# io2.net
KiCad netlist of a schematic drawn in EAGLE
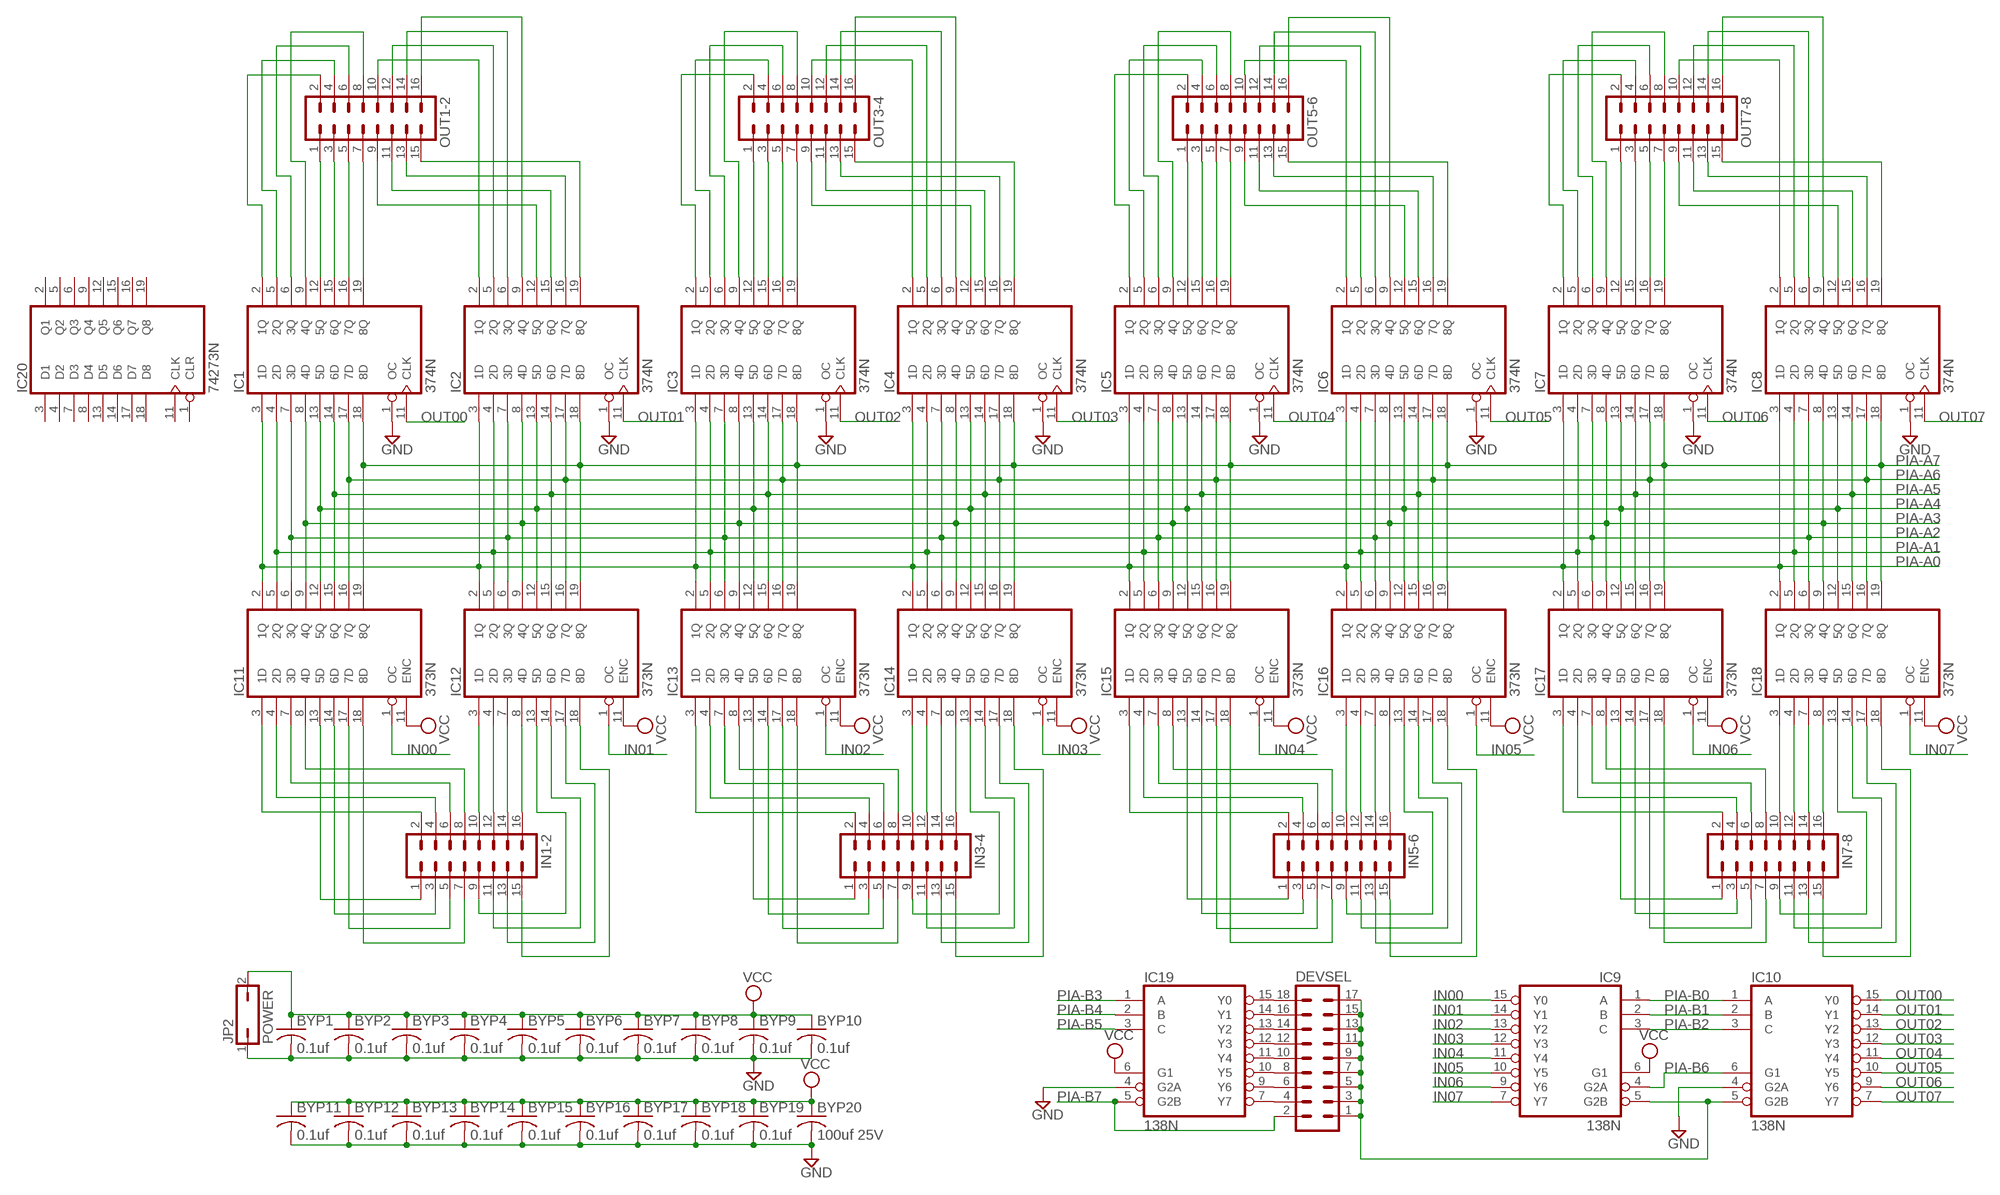
[diagram p0: schematic, sheet 1]
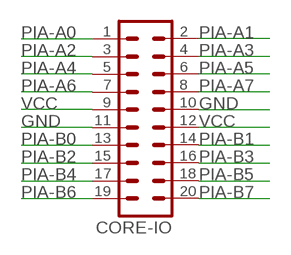
[diagram p1: schematic, sheet 2]

(export (version "E")
  (design (tool "Eeschema 10.0.6"))
  (components
    (comp (ref "CORE-IO")
      (value "MA10-2")
      (footprint "eagle-import:MA10-2")
      (libsource (lib "eagle-import") (part "MA10-2"))
    )
    (comp (ref "BYP1")
      (value "0.1uf")
      (footprint "eagle-import:C050-025X075")
      (libsource (lib "eagle-import") (part "C-US050-025X075"))
    )
    (comp (ref "BYP2")
      (value "0.1uf")
      (footprint "eagle-import:C050-025X075")
      (libsource (lib "eagle-import") (part "C-US050-025X075"))
    )
    (comp (ref "BYP3")
      (value "0.1uf")
      (footprint "eagle-import:C050-025X075")
      (libsource (lib "eagle-import") (part "C-US050-025X075"))
    )
    (comp (ref "BYP4")
      (value "0.1uf")
      (footprint "eagle-import:C050-025X075")
      (libsource (lib "eagle-import") (part "C-US050-025X075"))
    )
    (comp (ref "BYP5")
      (value "0.1uf")
      (footprint "eagle-import:C050-025X075")
      (libsource (lib "eagle-import") (part "C-US050-025X075"))
    )
    (comp (ref "BYP6")
      (value "0.1uf")
      (footprint "eagle-import:C050-025X075")
      (libsource (lib "eagle-import") (part "C-US050-025X075"))
    )
    (comp (ref "BYP7")
      (value "0.1uf")
      (footprint "eagle-import:C050-025X075")
      (libsource (lib "eagle-import") (part "C-US050-025X075"))
    )
    (comp (ref "BYP8")
      (value "0.1uf")
      (footprint "eagle-import:C050-025X075")
      (libsource (lib "eagle-import") (part "C-US050-025X075"))
    )
    (comp (ref "BYP9")
      (value "0.1uf")
      (footprint "eagle-import:C050-025X075")
      (libsource (lib "eagle-import") (part "C-US050-025X075"))
    )
    (comp (ref "BYP10")
      (value "0.1uf")
      (footprint "eagle-import:C050-025X075")
      (libsource (lib "eagle-import") (part "C-US050-025X075"))
    )
    (comp (ref "BYP11")
      (value "0.1uf")
      (footprint "eagle-import:C050-025X075")
      (libsource (lib "eagle-import") (part "C-US050-025X075"))
    )
    (comp (ref "BYP12")
      (value "0.1uf")
      (footprint "eagle-import:C050-025X075")
      (libsource (lib "eagle-import") (part "C-US050-025X075"))
    )
    (comp (ref "BYP13")
      (value "0.1uf")
      (footprint "eagle-import:C050-025X075")
      (libsource (lib "eagle-import") (part "C-US050-025X075"))
    )
    (comp (ref "BYP14")
      (value "0.1uf")
      (footprint "eagle-import:C050-025X075")
      (libsource (lib "eagle-import") (part "C-US050-025X075"))
    )
    (comp (ref "BYP15")
      (value "0.1uf")
      (footprint "eagle-import:C050-025X075")
      (libsource (lib "eagle-import") (part "C-US050-025X075"))
    )
    (comp (ref "BYP16")
      (value "0.1uf")
      (footprint "eagle-import:C050-025X075")
      (libsource (lib "eagle-import") (part "C-US050-025X075"))
    )
    (comp (ref "BYP17")
      (value "0.1uf")
      (footprint "eagle-import:C050-025X075")
      (libsource (lib "eagle-import") (part "C-US050-025X075"))
    )
    (comp (ref "BYP18")
      (value "0.1uf")
      (footprint "eagle-import:C050-025X075")
      (libsource (lib "eagle-import") (part "C-US050-025X075"))
    )
    (comp (ref "BYP19")
      (value "0.1uf")
      (footprint "eagle-import:C050-025X075")
      (libsource (lib "eagle-import") (part "C-US050-025X075"))
    )
    (comp (ref "BYP20")
      (value "100uf 25V")
      (footprint "eagle-import:C150-064X183")
      (libsource (lib "eagle-import") (part "C-US150-064X183"))
    )
    (comp (ref "DEVSEL")
      (value "MA09-2")
      (footprint "eagle-import:MA09-2")
      (libsource (lib "eagle-import") (part "MA09-2"))
    )
    (comp (ref "IC1")
      (value "374N")
      (footprint "eagle-import:DIL20")
      (libsource (lib "eagle-import") (part "74374NLS"))
    )
    (comp (ref "IC2")
      (value "374N")
      (footprint "eagle-import:DIL20")
      (libsource (lib "eagle-import") (part "74374NLS"))
    )
    (comp (ref "IC3")
      (value "374N")
      (footprint "eagle-import:DIL20")
      (libsource (lib "eagle-import") (part "74374NLS"))
    )
    (comp (ref "IC4")
      (value "374N")
      (footprint "eagle-import:DIL20")
      (libsource (lib "eagle-import") (part "74374NLS"))
    )
    (comp (ref "IC5")
      (value "374N")
      (footprint "eagle-import:DIL20")
      (libsource (lib "eagle-import") (part "74374NLS"))
    )
    (comp (ref "IC6")
      (value "374N")
      (footprint "eagle-import:DIL20")
      (libsource (lib "eagle-import") (part "74374NLS"))
    )
    (comp (ref "IC7")
      (value "374N")
      (footprint "eagle-import:DIL20")
      (libsource (lib "eagle-import") (part "74374NLS"))
    )
    (comp (ref "IC8")
      (value "374N")
      (footprint "eagle-import:DIL20")
      (libsource (lib "eagle-import") (part "74374NLS"))
    )
    (comp (ref "IC9")
      (value "138N")
      (footprint "eagle-import:DIL16")
      (libsource (lib "eagle-import") (part "74138NLS"))
    )
    (comp (ref "IC10")
      (value "138N")
      (footprint "eagle-import:DIL16")
      (libsource (lib "eagle-import") (part "74138NLS"))
    )
    (comp (ref "IC11")
      (value "373N")
      (footprint "eagle-import:DIL20")
      (libsource (lib "eagle-import") (part "74373NLS"))
    )
    (comp (ref "IC12")
      (value "373N")
      (footprint "eagle-import:DIL20")
      (libsource (lib "eagle-import") (part "74373NLS"))
    )
    (comp (ref "IC13")
      (value "373N")
      (footprint "eagle-import:DIL20")
      (libsource (lib "eagle-import") (part "74373NLS"))
    )
    (comp (ref "IC14")
      (value "373N")
      (footprint "eagle-import:DIL20")
      (libsource (lib "eagle-import") (part "74373NLS"))
    )
    (comp (ref "IC15")
      (value "373N")
      (footprint "eagle-import:DIL20")
      (libsource (lib "eagle-import") (part "74373NLS"))
    )
    (comp (ref "IC16")
      (value "373N")
      (footprint "eagle-import:DIL20")
      (libsource (lib "eagle-import") (part "74373NLS"))
    )
    (comp (ref "IC17")
      (value "373N")
      (footprint "eagle-import:DIL20")
      (libsource (lib "eagle-import") (part "74373NLS"))
    )
    (comp (ref "IC18")
      (value "373N")
      (footprint "eagle-import:DIL20")
      (libsource (lib "eagle-import") (part "74373NLS"))
    )
    (comp (ref "IC19")
      (value "138N")
      (footprint "eagle-import:DIL16")
      (libsource (lib "eagle-import") (part "74138NLS"))
    )
    (comp (ref "IC20")
      (value "74273N")
      (footprint "eagle-import:DIL20")
      (libsource (lib "eagle-import") (part "74273N"))
    )
    (comp (ref "IN1-2")
      (value "MA08-2")
      (footprint "eagle-import:MA08-2")
      (libsource (lib "eagle-import") (part "MA08-2"))
    )
    (comp (ref "IN3-4")
      (value "MA08-2")
      (footprint "eagle-import:MA08-2")
      (libsource (lib "eagle-import") (part "MA08-2"))
    )
    (comp (ref "IN5-6")
      (value "MA08-2")
      (footprint "eagle-import:MA08-2")
      (libsource (lib "eagle-import") (part "MA08-2"))
    )
    (comp (ref "IN7-8")
      (value "MA08-2")
      (footprint "eagle-import:MA08-2")
      (libsource (lib "eagle-import") (part "MA08-2"))
    )
    (comp (ref "JP2")
      (value "POWER")
      (footprint "eagle-import:JP1")
      (libsource (lib "eagle-import") (part "JP1Q"))
    )
    (comp (ref "OUT1-2")
      (value "MA08-2")
      (footprint "eagle-import:MA08-2")
      (libsource (lib "eagle-import") (part "MA08-2"))
    )
    (comp (ref "OUT3-4")
      (value "MA08-2")
      (footprint "eagle-import:MA08-2")
      (libsource (lib "eagle-import") (part "MA08-2"))
    )
    (comp (ref "OUT5-6")
      (value "MA08-2")
      (footprint "eagle-import:MA08-2")
      (libsource (lib "eagle-import") (part "MA08-2"))
    )
    (comp (ref "OUT7-8")
      (value "MA08-2")
      (footprint "eagle-import:MA08-2")
      (libsource (lib "eagle-import") (part "MA08-2"))
    )
  )
  (nets
    (net (code "1") (name "GND") (class "Default")
      (node (ref "BYP1") (pin "2") (pinfunction "2_2") (pintype "passive"))
      (node (ref "BYP10") (pin "2") (pinfunction "2_2") (pintype "passive"))
      (node (ref "BYP11") (pin "2") (pinfunction "2_2") (pintype "passive"))
      (node (ref "BYP12") (pin "2") (pinfunction "2_2") (pintype "passive"))
      (node (ref "BYP13") (pin "2") (pinfunction "2_2") (pintype "passive"))
      (node (ref "BYP14") (pin "2") (pinfunction "2_2") (pintype "passive"))
      (node (ref "BYP15") (pin "2") (pinfunction "2_2") (pintype "passive"))
      (node (ref "BYP16") (pin "2") (pinfunction "2_2") (pintype "passive"))
      (node (ref "BYP17") (pin "2") (pinfunction "2_2") (pintype "passive"))
      (node (ref "BYP18") (pin "2") (pinfunction "2_2") (pintype "passive"))
      (node (ref "BYP19") (pin "2") (pinfunction "2_2") (pintype "passive"))
      (node (ref "BYP2") (pin "2") (pinfunction "2_2") (pintype "passive"))
      (node (ref "BYP20") (pin "2") (pinfunction "2_2") (pintype "passive"))
      (node (ref "BYP3") (pin "2") (pinfunction "2_2") (pintype "passive"))
      (node (ref "BYP4") (pin "2") (pinfunction "2_2") (pintype "passive"))
      (node (ref "BYP5") (pin "2") (pinfunction "2_2") (pintype "passive"))
      (node (ref "BYP6") (pin "2") (pinfunction "2_2") (pintype "passive"))
      (node (ref "BYP7") (pin "2") (pinfunction "2_2") (pintype "passive"))
      (node (ref "BYP8") (pin "2") (pinfunction "2_2") (pintype "passive"))
      (node (ref "BYP9") (pin "2") (pinfunction "2_2") (pintype "passive"))
      (node (ref "CORE-IO") (pin "10") (pinfunction "10_10") (pintype "passive"))
      (node (ref "CORE-IO") (pin "11") (pinfunction "11_11") (pintype "passive"))
      (node (ref "IC1") (pin "1") (pinfunction "OC_1") (pintype "input"))
      (node (ref "IC10") (pin "4") (pinfunction "G2A_4") (pintype "input"))
      (node (ref "IC19") (pin "4") (pinfunction "G2A_4") (pintype "input"))
      (node (ref "IC2") (pin "1") (pinfunction "OC_1") (pintype "input"))
      (node (ref "IC3") (pin "1") (pinfunction "OC_1") (pintype "input"))
      (node (ref "IC4") (pin "1") (pinfunction "OC_1") (pintype "input"))
      (node (ref "IC5") (pin "1") (pinfunction "OC_1") (pintype "input"))
      (node (ref "IC6") (pin "1") (pinfunction "OC_1") (pintype "input"))
      (node (ref "IC7") (pin "1") (pinfunction "OC_1") (pintype "input"))
      (node (ref "IC8") (pin "1") (pinfunction "OC_1") (pintype "input"))
      (node (ref "JP2") (pin "1") (pinfunction "1_1") (pintype "passive"))
    )
    (net (code "2") (name "IN00") (class "Default")
      (node (ref "IC11") (pin "1") (pinfunction "OC_1") (pintype "input"))
      (node (ref "IC9") (pin "15") (pinfunction "Y0_15") (pintype "output"))
    )
    (net (code "3") (name "IN01") (class "Default")
      (node (ref "IC12") (pin "1") (pinfunction "OC_1") (pintype "input"))
      (node (ref "IC9") (pin "14") (pinfunction "Y1_14") (pintype "output"))
    )
    (net (code "4") (name "IN02") (class "Default")
      (node (ref "IC13") (pin "1") (pinfunction "OC_1") (pintype "input"))
      (node (ref "IC9") (pin "13") (pinfunction "Y2_13") (pintype "output"))
    )
    (net (code "5") (name "IN03") (class "Default")
      (node (ref "IC14") (pin "1") (pinfunction "OC_1") (pintype "input"))
      (node (ref "IC9") (pin "12") (pinfunction "Y3_12") (pintype "output"))
    )
    (net (code "6") (name "IN04") (class "Default")
      (node (ref "IC15") (pin "1") (pinfunction "OC_1") (pintype "input"))
      (node (ref "IC9") (pin "11") (pinfunction "Y4_11") (pintype "output"))
    )
    (net (code "7") (name "IN05") (class "Default")
      (node (ref "IC16") (pin "1") (pinfunction "OC_1") (pintype "input"))
      (node (ref "IC9") (pin "10") (pinfunction "Y5_10") (pintype "output"))
    )
    (net (code "8") (name "IN06") (class "Default")
      (node (ref "IC17") (pin "1") (pinfunction "OC_1") (pintype "input"))
      (node (ref "IC9") (pin "9") (pinfunction "Y6_9") (pintype "output"))
    )
    (net (code "9") (name "IN07") (class "Default")
      (node (ref "IC18") (pin "1") (pinfunction "OC_1") (pintype "input"))
      (node (ref "IC9") (pin "7") (pinfunction "Y7_7") (pintype "output"))
    )
    (net (code "10") (name "Net-(IC1A-1Q)") (class "Default")
      (node (ref "IC1") (pin "2") (pinfunction "1Q_2") (pintype "tri_state"))
      (node (ref "OUT1-2") (pin "2") (pinfunction "2_2") (pintype "passive"))
    )
    (net (code "11") (name "Net-(IC1A-2Q)") (class "Default")
      (node (ref "IC1") (pin "5") (pinfunction "2Q_5") (pintype "tri_state"))
      (node (ref "OUT1-2") (pin "4") (pinfunction "4_4") (pintype "passive"))
    )
    (net (code "12") (name "Net-(IC1A-3Q)") (class "Default")
      (node (ref "IC1") (pin "6") (pinfunction "3Q_6") (pintype "tri_state"))
      (node (ref "OUT1-2") (pin "6") (pinfunction "6_6") (pintype "passive"))
    )
    (net (code "13") (name "Net-(IC1A-4Q)") (class "Default")
      (node (ref "IC1") (pin "9") (pinfunction "4Q_9") (pintype "tri_state"))
      (node (ref "OUT1-2") (pin "8") (pinfunction "8_8") (pintype "passive"))
    )
    (net (code "14") (name "Net-(IC1A-5Q)") (class "Default")
      (node (ref "IC1") (pin "12") (pinfunction "5Q_12") (pintype "tri_state"))
      (node (ref "OUT1-2") (pin "1") (pinfunction "1_1") (pintype "passive"))
    )
    (net (code "15") (name "Net-(IC1A-6Q)") (class "Default")
      (node (ref "IC1") (pin "15") (pinfunction "6Q_15") (pintype "tri_state"))
      (node (ref "OUT1-2") (pin "3") (pinfunction "3_3") (pintype "passive"))
    )
    (net (code "16") (name "Net-(IC1A-7Q)") (class "Default")
      (node (ref "IC1") (pin "16") (pinfunction "7Q_16") (pintype "tri_state"))
      (node (ref "OUT1-2") (pin "5") (pinfunction "5_5") (pintype "passive"))
    )
    (net (code "17") (name "Net-(IC1A-8Q)") (class "Default")
      (node (ref "IC1") (pin "19") (pinfunction "8Q_19") (pintype "tri_state"))
      (node (ref "OUT1-2") (pin "7") (pinfunction "7_7") (pintype "passive"))
    )
    (net (code "18") (name "Net-(IC2A-1Q)") (class "Default")
      (node (ref "IC2") (pin "2") (pinfunction "1Q_2") (pintype "tri_state"))
      (node (ref "OUT1-2") (pin "10") (pinfunction "10_10") (pintype "passive"))
    )
    (net (code "19") (name "Net-(IC2A-2Q)") (class "Default")
      (node (ref "IC2") (pin "5") (pinfunction "2Q_5") (pintype "tri_state"))
      (node (ref "OUT1-2") (pin "12") (pinfunction "12_12") (pintype "passive"))
    )
    (net (code "20") (name "Net-(IC2A-3Q)") (class "Default")
      (node (ref "IC2") (pin "6") (pinfunction "3Q_6") (pintype "tri_state"))
      (node (ref "OUT1-2") (pin "14") (pinfunction "14_14") (pintype "passive"))
    )
    (net (code "21") (name "Net-(IC2A-4Q)") (class "Default")
      (node (ref "IC2") (pin "9") (pinfunction "4Q_9") (pintype "tri_state"))
      (node (ref "OUT1-2") (pin "16") (pinfunction "16_16") (pintype "passive"))
    )
    (net (code "22") (name "Net-(IC2A-5Q)") (class "Default")
      (node (ref "IC2") (pin "12") (pinfunction "5Q_12") (pintype "tri_state"))
      (node (ref "OUT1-2") (pin "9") (pinfunction "9_9") (pintype "passive"))
    )
    (net (code "23") (name "Net-(IC2A-6Q)") (class "Default")
      (node (ref "IC2") (pin "15") (pinfunction "6Q_15") (pintype "tri_state"))
      (node (ref "OUT1-2") (pin "11") (pinfunction "11_11") (pintype "passive"))
    )
    (net (code "24") (name "Net-(IC2A-7Q)") (class "Default")
      (node (ref "IC2") (pin "16") (pinfunction "7Q_16") (pintype "tri_state"))
      (node (ref "OUT1-2") (pin "13") (pinfunction "13_13") (pintype "passive"))
    )
    (net (code "25") (name "Net-(IC2A-8Q)") (class "Default")
      (node (ref "IC2") (pin "19") (pinfunction "8Q_19") (pintype "tri_state"))
      (node (ref "OUT1-2") (pin "15") (pinfunction "15_15") (pintype "passive"))
    )
    (net (code "26") (name "Net-(IC3A-1Q)") (class "Default")
      (node (ref "IC3") (pin "2") (pinfunction "1Q_2") (pintype "tri_state"))
      (node (ref "OUT3-4") (pin "2") (pinfunction "2_2") (pintype "passive"))
    )
    (net (code "27") (name "Net-(IC3A-2Q)") (class "Default")
      (node (ref "IC3") (pin "5") (pinfunction "2Q_5") (pintype "tri_state"))
      (node (ref "OUT3-4") (pin "4") (pinfunction "4_4") (pintype "passive"))
    )
    (net (code "28") (name "Net-(IC3A-3Q)") (class "Default")
      (node (ref "IC3") (pin "6") (pinfunction "3Q_6") (pintype "tri_state"))
      (node (ref "OUT3-4") (pin "6") (pinfunction "6_6") (pintype "passive"))
    )
    (net (code "29") (name "Net-(IC3A-4Q)") (class "Default")
      (node (ref "IC3") (pin "9") (pinfunction "4Q_9") (pintype "tri_state"))
      (node (ref "OUT3-4") (pin "8") (pinfunction "8_8") (pintype "passive"))
    )
    (net (code "30") (name "Net-(IC3A-5Q)") (class "Default")
      (node (ref "IC3") (pin "12") (pinfunction "5Q_12") (pintype "tri_state"))
      (node (ref "OUT3-4") (pin "1") (pinfunction "1_1") (pintype "passive"))
    )
    (net (code "31") (name "Net-(IC3A-6Q)") (class "Default")
      (node (ref "IC3") (pin "15") (pinfunction "6Q_15") (pintype "tri_state"))
      (node (ref "OUT3-4") (pin "3") (pinfunction "3_3") (pintype "passive"))
    )
    (net (code "32") (name "Net-(IC3A-7Q)") (class "Default")
      (node (ref "IC3") (pin "16") (pinfunction "7Q_16") (pintype "tri_state"))
      (node (ref "OUT3-4") (pin "5") (pinfunction "5_5") (pintype "passive"))
    )
    (net (code "33") (name "Net-(IC3A-8Q)") (class "Default")
      (node (ref "IC3") (pin "19") (pinfunction "8Q_19") (pintype "tri_state"))
      (node (ref "OUT3-4") (pin "7") (pinfunction "7_7") (pintype "passive"))
    )
    (net (code "34") (name "Net-(IC4A-1Q)") (class "Default")
      (node (ref "IC4") (pin "2") (pinfunction "1Q_2") (pintype "tri_state"))
      (node (ref "OUT3-4") (pin "10") (pinfunction "10_10") (pintype "passive"))
    )
    (net (code "35") (name "Net-(IC4A-2Q)") (class "Default")
      (node (ref "IC4") (pin "5") (pinfunction "2Q_5") (pintype "tri_state"))
      (node (ref "OUT3-4") (pin "12") (pinfunction "12_12") (pintype "passive"))
    )
    (net (code "36") (name "Net-(IC4A-3Q)") (class "Default")
      (node (ref "IC4") (pin "6") (pinfunction "3Q_6") (pintype "tri_state"))
      (node (ref "OUT3-4") (pin "14") (pinfunction "14_14") (pintype "passive"))
    )
    (net (code "37") (name "Net-(IC4A-4Q)") (class "Default")
      (node (ref "IC4") (pin "9") (pinfunction "4Q_9") (pintype "tri_state"))
      (node (ref "OUT3-4") (pin "16") (pinfunction "16_16") (pintype "passive"))
    )
    (net (code "38") (name "Net-(IC4A-5Q)") (class "Default")
      (node (ref "IC4") (pin "12") (pinfunction "5Q_12") (pintype "tri_state"))
      (node (ref "OUT3-4") (pin "9") (pinfunction "9_9") (pintype "passive"))
    )
    (net (code "39") (name "Net-(IC4A-6Q)") (class "Default")
      (node (ref "IC4") (pin "15") (pinfunction "6Q_15") (pintype "tri_state"))
      (node (ref "OUT3-4") (pin "11") (pinfunction "11_11") (pintype "passive"))
    )
    (net (code "40") (name "Net-(IC4A-7Q)") (class "Default")
      (node (ref "IC4") (pin "16") (pinfunction "7Q_16") (pintype "tri_state"))
      (node (ref "OUT3-4") (pin "13") (pinfunction "13_13") (pintype "passive"))
    )
    (net (code "41") (name "Net-(IC4A-8Q)") (class "Default")
      (node (ref "IC4") (pin "19") (pinfunction "8Q_19") (pintype "tri_state"))
      (node (ref "OUT3-4") (pin "15") (pinfunction "15_15") (pintype "passive"))
    )
    (net (code "42") (name "Net-(IC5A-1Q)") (class "Default")
      (node (ref "IC5") (pin "2") (pinfunction "1Q_2") (pintype "tri_state"))
      (node (ref "OUT5-6") (pin "2") (pinfunction "2_2") (pintype "passive"))
    )
    (net (code "43") (name "Net-(IC5A-2Q)") (class "Default")
      (node (ref "IC5") (pin "5") (pinfunction "2Q_5") (pintype "tri_state"))
      (node (ref "OUT5-6") (pin "4") (pinfunction "4_4") (pintype "passive"))
    )
    (net (code "44") (name "Net-(IC5A-3Q)") (class "Default")
      (node (ref "IC5") (pin "6") (pinfunction "3Q_6") (pintype "tri_state"))
      (node (ref "OUT5-6") (pin "6") (pinfunction "6_6") (pintype "passive"))
    )
    (net (code "45") (name "Net-(IC5A-4Q)") (class "Default")
      (node (ref "IC5") (pin "9") (pinfunction "4Q_9") (pintype "tri_state"))
      (node (ref "OUT5-6") (pin "8") (pinfunction "8_8") (pintype "passive"))
    )
    (net (code "46") (name "Net-(IC5A-5Q)") (class "Default")
      (node (ref "IC5") (pin "12") (pinfunction "5Q_12") (pintype "tri_state"))
      (node (ref "OUT5-6") (pin "1") (pinfunction "1_1") (pintype "passive"))
    )
    (net (code "47") (name "Net-(IC5A-6Q)") (class "Default")
      (node (ref "IC5") (pin "15") (pinfunction "6Q_15") (pintype "tri_state"))
      (node (ref "OUT5-6") (pin "3") (pinfunction "3_3") (pintype "passive"))
    )
    (net (code "48") (name "Net-(IC5A-7Q)") (class "Default")
      (node (ref "IC5") (pin "16") (pinfunction "7Q_16") (pintype "tri_state"))
      (node (ref "OUT5-6") (pin "5") (pinfunction "5_5") (pintype "passive"))
    )
    (net (code "49") (name "Net-(IC5A-8Q)") (class "Default")
      (node (ref "IC5") (pin "19") (pinfunction "8Q_19") (pintype "tri_state"))
      (node (ref "OUT5-6") (pin "7") (pinfunction "7_7") (pintype "passive"))
    )
    (net (code "50") (name "Net-(IC6A-1Q)") (class "Default")
      (node (ref "IC6") (pin "2") (pinfunction "1Q_2") (pintype "tri_state"))
      (node (ref "OUT5-6") (pin "10") (pinfunction "10_10") (pintype "passive"))
    )
    (net (code "51") (name "Net-(IC6A-2Q)") (class "Default")
      (node (ref "IC6") (pin "5") (pinfunction "2Q_5") (pintype "tri_state"))
      (node (ref "OUT5-6") (pin "12") (pinfunction "12_12") (pintype "passive"))
    )
    (net (code "52") (name "Net-(IC6A-3Q)") (class "Default")
      (node (ref "IC6") (pin "6") (pinfunction "3Q_6") (pintype "tri_state"))
      (node (ref "OUT5-6") (pin "14") (pinfunction "14_14") (pintype "passive"))
    )
    (net (code "53") (name "Net-(IC6A-4Q)") (class "Default")
      (node (ref "IC6") (pin "9") (pinfunction "4Q_9") (pintype "tri_state"))
      (node (ref "OUT5-6") (pin "16") (pinfunction "16_16") (pintype "passive"))
    )
    (net (code "54") (name "Net-(IC6A-5Q)") (class "Default")
      (node (ref "IC6") (pin "12") (pinfunction "5Q_12") (pintype "tri_state"))
      (node (ref "OUT5-6") (pin "9") (pinfunction "9_9") (pintype "passive"))
    )
    (net (code "55") (name "Net-(IC6A-6Q)") (class "Default")
      (node (ref "IC6") (pin "15") (pinfunction "6Q_15") (pintype "tri_state"))
      (node (ref "OUT5-6") (pin "11") (pinfunction "11_11") (pintype "passive"))
    )
    (net (code "56") (name "Net-(IC6A-7Q)") (class "Default")
      (node (ref "IC6") (pin "16") (pinfunction "7Q_16") (pintype "tri_state"))
      (node (ref "OUT5-6") (pin "13") (pinfunction "13_13") (pintype "passive"))
    )
    (net (code "57") (name "Net-(IC6A-8Q)") (class "Default")
      (node (ref "IC6") (pin "19") (pinfunction "8Q_19") (pintype "tri_state"))
      (node (ref "OUT5-6") (pin "15") (pinfunction "15_15") (pintype "passive"))
    )
    (net (code "58") (name "Net-(IC7A-1Q)") (class "Default")
      (node (ref "IC7") (pin "2") (pinfunction "1Q_2") (pintype "tri_state"))
      (node (ref "OUT7-8") (pin "2") (pinfunction "2_2") (pintype "passive"))
    )
    (net (code "59") (name "Net-(IC7A-2Q)") (class "Default")
      (node (ref "IC7") (pin "5") (pinfunction "2Q_5") (pintype "tri_state"))
      (node (ref "OUT7-8") (pin "4") (pinfunction "4_4") (pintype "passive"))
    )
    (net (code "60") (name "Net-(IC7A-3Q)") (class "Default")
      (node (ref "IC7") (pin "6") (pinfunction "3Q_6") (pintype "tri_state"))
      (node (ref "OUT7-8") (pin "6") (pinfunction "6_6") (pintype "passive"))
    )
    (net (code "61") (name "Net-(IC7A-4Q)") (class "Default")
      (node (ref "IC7") (pin "9") (pinfunction "4Q_9") (pintype "tri_state"))
      (node (ref "OUT7-8") (pin "8") (pinfunction "8_8") (pintype "passive"))
    )
    (net (code "62") (name "Net-(IC7A-5Q)") (class "Default")
      (node (ref "IC7") (pin "12") (pinfunction "5Q_12") (pintype "tri_state"))
      (node (ref "OUT7-8") (pin "1") (pinfunction "1_1") (pintype "passive"))
    )
    (net (code "63") (name "Net-(IC7A-6Q)") (class "Default")
      (node (ref "IC7") (pin "15") (pinfunction "6Q_15") (pintype "tri_state"))
      (node (ref "OUT7-8") (pin "3") (pinfunction "3_3") (pintype "passive"))
    )
    (net (code "64") (name "Net-(IC7A-7Q)") (class "Default")
      (node (ref "IC7") (pin "16") (pinfunction "7Q_16") (pintype "tri_state"))
      (node (ref "OUT7-8") (pin "5") (pinfunction "5_5") (pintype "passive"))
    )
    (net (code "65") (name "Net-(IC7A-8Q)") (class "Default")
      (node (ref "IC7") (pin "19") (pinfunction "8Q_19") (pintype "tri_state"))
      (node (ref "OUT7-8") (pin "7") (pinfunction "7_7") (pintype "passive"))
    )
    (net (code "66") (name "Net-(IC8A-1Q)") (class "Default")
      (node (ref "IC8") (pin "2") (pinfunction "1Q_2") (pintype "tri_state"))
      (node (ref "OUT7-8") (pin "10") (pinfunction "10_10") (pintype "passive"))
    )
    (net (code "67") (name "Net-(IC8A-2Q)") (class "Default")
      (node (ref "IC8") (pin "5") (pinfunction "2Q_5") (pintype "tri_state"))
      (node (ref "OUT7-8") (pin "12") (pinfunction "12_12") (pintype "passive"))
    )
    (net (code "68") (name "Net-(IC8A-3Q)") (class "Default")
      (node (ref "IC8") (pin "6") (pinfunction "3Q_6") (pintype "tri_state"))
      (node (ref "OUT7-8") (pin "14") (pinfunction "14_14") (pintype "passive"))
    )
    (net (code "69") (name "Net-(IC8A-4Q)") (class "Default")
      (node (ref "IC8") (pin "9") (pinfunction "4Q_9") (pintype "tri_state"))
      (node (ref "OUT7-8") (pin "16") (pinfunction "16_16") (pintype "passive"))
    )
    (net (code "70") (name "Net-(IC8A-5Q)") (class "Default")
      (node (ref "IC8") (pin "12") (pinfunction "5Q_12") (pintype "tri_state"))
      (node (ref "OUT7-8") (pin "9") (pinfunction "9_9") (pintype "passive"))
    )
    (net (code "71") (name "Net-(IC8A-6Q)") (class "Default")
      (node (ref "IC8") (pin "15") (pinfunction "6Q_15") (pintype "tri_state"))
      (node (ref "OUT7-8") (pin "11") (pinfunction "11_11") (pintype "passive"))
    )
    (net (code "72") (name "Net-(IC8A-7Q)") (class "Default")
      (node (ref "IC8") (pin "16") (pinfunction "7Q_16") (pintype "tri_state"))
      (node (ref "OUT7-8") (pin "13") (pinfunction "13_13") (pintype "passive"))
    )
    (net (code "73") (name "Net-(IC8A-8Q)") (class "Default")
      (node (ref "IC8") (pin "19") (pinfunction "8Q_19") (pintype "tri_state"))
      (node (ref "OUT7-8") (pin "15") (pinfunction "15_15") (pintype "passive"))
    )
    (net (code "74") (name "Net-(IC10A-G2B)") (class "Default")
      (node (ref "DEVSEL") (pin "1") (pinfunction "1_1") (pintype "passive"))
      (node (ref "DEVSEL") (pin "11") (pinfunction "11_11") (pintype "passive"))
      (node (ref "DEVSEL") (pin "13") (pinfunction "13_13") (pintype "passive"))
      (node (ref "DEVSEL") (pin "15") (pinfunction "15_15") (pintype "passive"))
      (node (ref "DEVSEL") (pin "17") (pinfunction "17_17") (pintype "passive"))
      (node (ref "DEVSEL") (pin "3") (pinfunction "3_3") (pintype "passive"))
      (node (ref "DEVSEL") (pin "5") (pinfunction "5_5") (pintype "passive"))
      (node (ref "DEVSEL") (pin "7") (pinfunction "7_7") (pintype "passive"))
      (node (ref "DEVSEL") (pin "9") (pinfunction "9_9") (pintype "passive"))
      (node (ref "IC10") (pin "5") (pinfunction "G2B_5") (pintype "input"))
      (node (ref "IC9") (pin "5") (pinfunction "G2B_5") (pintype "input"))
    )
    (net (code "75") (name "Net-(IC11A-1D)") (class "Default")
      (node (ref "IC11") (pin "3") (pinfunction "1D_3") (pintype "input"))
      (node (ref "IN1-2") (pin "2") (pinfunction "2_2") (pintype "passive"))
    )
    (net (code "76") (name "Net-(IC11A-2D)") (class "Default")
      (node (ref "IC11") (pin "4") (pinfunction "2D_4") (pintype "input"))
      (node (ref "IN1-2") (pin "4") (pinfunction "4_4") (pintype "passive"))
    )
    (net (code "77") (name "Net-(IC11A-3D)") (class "Default")
      (node (ref "IC11") (pin "7") (pinfunction "3D_7") (pintype "input"))
      (node (ref "IN1-2") (pin "6") (pinfunction "6_6") (pintype "passive"))
    )
    (net (code "78") (name "Net-(IC11A-4D)") (class "Default")
      (node (ref "IC11") (pin "8") (pinfunction "4D_8") (pintype "input"))
      (node (ref "IN1-2") (pin "8") (pinfunction "8_8") (pintype "passive"))
    )
    (net (code "79") (name "Net-(IC11A-5D)") (class "Default")
      (node (ref "IC11") (pin "13") (pinfunction "5D_13") (pintype "input"))
      (node (ref "IN1-2") (pin "1") (pinfunction "1_1") (pintype "passive"))
    )
    (net (code "80") (name "Net-(IC11A-6D)") (class "Default")
      (node (ref "IC11") (pin "14") (pinfunction "6D_14") (pintype "input"))
      (node (ref "IN1-2") (pin "3") (pinfunction "3_3") (pintype "passive"))
    )
    (net (code "81") (name "Net-(IC11A-7D)") (class "Default")
      (node (ref "IC11") (pin "17") (pinfunction "7D_17") (pintype "input"))
      (node (ref "IN1-2") (pin "5") (pinfunction "5_5") (pintype "passive"))
    )
    (net (code "82") (name "Net-(IC11A-8D)") (class "Default")
      (node (ref "IC11") (pin "18") (pinfunction "8D_18") (pintype "input"))
      (node (ref "IN1-2") (pin "7") (pinfunction "7_7") (pintype "passive"))
    )
    (net (code "83") (name "Net-(IC12A-1D)") (class "Default")
      (node (ref "IC12") (pin "3") (pinfunction "1D_3") (pintype "input"))
      (node (ref "IN1-2") (pin "10") (pinfunction "10_10") (pintype "passive"))
    )
    (net (code "84") (name "Net-(IC12A-2D)") (class "Default")
      (node (ref "IC12") (pin "4") (pinfunction "2D_4") (pintype "input"))
      (node (ref "IN1-2") (pin "12") (pinfunction "12_12") (pintype "passive"))
    )
    (net (code "85") (name "Net-(IC12A-3D)") (class "Default")
      (node (ref "IC12") (pin "7") (pinfunction "3D_7") (pintype "input"))
      (node (ref "IN1-2") (pin "14") (pinfunction "14_14") (pintype "passive"))
    )
    (net (code "86") (name "Net-(IC12A-4D)") (class "Default")
      (node (ref "IC12") (pin "8") (pinfunction "4D_8") (pintype "input"))
      (node (ref "IN1-2") (pin "16") (pinfunction "16_16") (pintype "passive"))
    )
    (net (code "87") (name "Net-(IC12A-5D)") (class "Default")
      (node (ref "IC12") (pin "13") (pinfunction "5D_13") (pintype "input"))
      (node (ref "IN1-2") (pin "9") (pinfunction "9_9") (pintype "passive"))
    )
    (net (code "88") (name "Net-(IC12A-6D)") (class "Default")
      (node (ref "IC12") (pin "14") (pinfunction "6D_14") (pintype "input"))
      (node (ref "IN1-2") (pin "11") (pinfunction "11_11") (pintype "passive"))
    )
    (net (code "89") (name "Net-(IC12A-7D)") (class "Default")
      (node (ref "IC12") (pin "17") (pinfunction "7D_17") (pintype "input"))
      (node (ref "IN1-2") (pin "13") (pinfunction "13_13") (pintype "passive"))
    )
    (net (code "90") (name "Net-(IC12A-8D)") (class "Default")
      (node (ref "IC12") (pin "18") (pinfunction "8D_18") (pintype "input"))
      (node (ref "IN1-2") (pin "15") (pinfunction "15_15") (pintype "passive"))
    )
    (net (code "91") (name "Net-(IC13A-1D)") (class "Default")
      (node (ref "IC13") (pin "3") (pinfunction "1D_3") (pintype "input"))
      (node (ref "IN3-4") (pin "2") (pinfunction "2_2") (pintype "passive"))
    )
    (net (code "92") (name "Net-(IC13A-2D)") (class "Default")
      (node (ref "IC13") (pin "4") (pinfunction "2D_4") (pintype "input"))
      (node (ref "IN3-4") (pin "4") (pinfunction "4_4") (pintype "passive"))
    )
    (net (code "93") (name "Net-(IC13A-3D)") (class "Default")
      (node (ref "IC13") (pin "7") (pinfunction "3D_7") (pintype "input"))
      (node (ref "IN3-4") (pin "6") (pinfunction "6_6") (pintype "passive"))
    )
    (net (code "94") (name "Net-(IC13A-4D)") (class "Default")
      (node (ref "IC13") (pin "8") (pinfunction "4D_8") (pintype "input"))
      (node (ref "IN3-4") (pin "8") (pinfunction "8_8") (pintype "passive"))
    )
    (net (code "95") (name "Net-(IC13A-5D)") (class "Default")
      (node (ref "IC13") (pin "13") (pinfunction "5D_13") (pintype "input"))
      (node (ref "IN3-4") (pin "1") (pinfunction "1_1") (pintype "passive"))
    )
    (net (code "96") (name "Net-(IC13A-6D)") (class "Default")
      (node (ref "IC13") (pin "14") (pinfunction "6D_14") (pintype "input"))
      (node (ref "IN3-4") (pin "3") (pinfunction "3_3") (pintype "passive"))
    )
    (net (code "97") (name "Net-(IC13A-7D)") (class "Default")
      (node (ref "IC13") (pin "17") (pinfunction "7D_17") (pintype "input"))
      (node (ref "IN3-4") (pin "5") (pinfunction "5_5") (pintype "passive"))
    )
    (net (code "98") (name "Net-(IC13A-8D)") (class "Default")
      (node (ref "IC13") (pin "18") (pinfunction "8D_18") (pintype "input"))
      (node (ref "IN3-4") (pin "7") (pinfunction "7_7") (pintype "passive"))
    )
    (net (code "99") (name "Net-(IC14A-1D)") (class "Default")
      (node (ref "IC14") (pin "3") (pinfunction "1D_3") (pintype "input"))
      (node (ref "IN3-4") (pin "10") (pinfunction "10_10") (pintype "passive"))
    )
    (net (code "100") (name "Net-(IC14A-2D)") (class "Default")
      (node (ref "IC14") (pin "4") (pinfunction "2D_4") (pintype "input"))
      (node (ref "IN3-4") (pin "12") (pinfunction "12_12") (pintype "passive"))
    )
    (net (code "101") (name "Net-(IC14A-3D)") (class "Default")
      (node (ref "IC14") (pin "7") (pinfunction "3D_7") (pintype "input"))
      (node (ref "IN3-4") (pin "14") (pinfunction "14_14") (pintype "passive"))
    )
    (net (code "102") (name "Net-(IC14A-4D)") (class "Default")
      (node (ref "IC14") (pin "8") (pinfunction "4D_8") (pintype "input"))
      (node (ref "IN3-4") (pin "16") (pinfunction "16_16") (pintype "passive"))
    )
    (net (code "103") (name "Net-(IC14A-5D)") (class "Default")
      (node (ref "IC14") (pin "13") (pinfunction "5D_13") (pintype "input"))
      (node (ref "IN3-4") (pin "9") (pinfunction "9_9") (pintype "passive"))
    )
    (net (code "104") (name "Net-(IC14A-6D)") (class "Default")
      (node (ref "IC14") (pin "14") (pinfunction "6D_14") (pintype "input"))
      (node (ref "IN3-4") (pin "11") (pinfunction "11_11") (pintype "passive"))
    )
    (net (code "105") (name "Net-(IC14A-7D)") (class "Default")
      (node (ref "IC14") (pin "17") (pinfunction "7D_17") (pintype "input"))
      (node (ref "IN3-4") (pin "13") (pinfunction "13_13") (pintype "passive"))
    )
    (net (code "106") (name "Net-(IC14A-8D)") (class "Default")
      (node (ref "IC14") (pin "18") (pinfunction "8D_18") (pintype "input"))
      (node (ref "IN3-4") (pin "15") (pinfunction "15_15") (pintype "passive"))
    )
    (net (code "107") (name "Net-(IC15A-1D)") (class "Default")
      (node (ref "IC15") (pin "3") (pinfunction "1D_3") (pintype "input"))
      (node (ref "IN5-6") (pin "2") (pinfunction "2_2") (pintype "passive"))
    )
    (net (code "108") (name "Net-(IC15A-2D)") (class "Default")
      (node (ref "IC15") (pin "4") (pinfunction "2D_4") (pintype "input"))
      (node (ref "IN5-6") (pin "4") (pinfunction "4_4") (pintype "passive"))
    )
    (net (code "109") (name "Net-(IC15A-3D)") (class "Default")
      (node (ref "IC15") (pin "7") (pinfunction "3D_7") (pintype "input"))
      (node (ref "IN5-6") (pin "6") (pinfunction "6_6") (pintype "passive"))
    )
    (net (code "110") (name "Net-(IC15A-4D)") (class "Default")
      (node (ref "IC15") (pin "8") (pinfunction "4D_8") (pintype "input"))
      (node (ref "IN5-6") (pin "8") (pinfunction "8_8") (pintype "passive"))
    )
    (net (code "111") (name "Net-(IC15A-5D)") (class "Default")
      (node (ref "IC15") (pin "13") (pinfunction "5D_13") (pintype "input"))
      (node (ref "IN5-6") (pin "1") (pinfunction "1_1") (pintype "passive"))
    )
    (net (code "112") (name "Net-(IC15A-6D)") (class "Default")
      (node (ref "IC15") (pin "14") (pinfunction "6D_14") (pintype "input"))
      (node (ref "IN5-6") (pin "3") (pinfunction "3_3") (pintype "passive"))
    )
    (net (code "113") (name "Net-(IC15A-7D)") (class "Default")
      (node (ref "IC15") (pin "17") (pinfunction "7D_17") (pintype "input"))
      (node (ref "IN5-6") (pin "5") (pinfunction "5_5") (pintype "passive"))
    )
    (net (code "114") (name "Net-(IC15A-8D)") (class "Default")
      (node (ref "IC15") (pin "18") (pinfunction "8D_18") (pintype "input"))
      (node (ref "IN5-6") (pin "7") (pinfunction "7_7") (pintype "passive"))
    )
    (net (code "115") (name "Net-(IC16A-1D)") (class "Default")
      (node (ref "IC16") (pin "3") (pinfunction "1D_3") (pintype "input"))
      (node (ref "IN5-6") (pin "10") (pinfunction "10_10") (pintype "passive"))
    )
    (net (code "116") (name "Net-(IC16A-2D)") (class "Default")
      (node (ref "IC16") (pin "4") (pinfunction "2D_4") (pintype "input"))
      (node (ref "IN5-6") (pin "12") (pinfunction "12_12") (pintype "passive"))
    )
    (net (code "117") (name "Net-(IC16A-3D)") (class "Default")
      (node (ref "IC16") (pin "7") (pinfunction "3D_7") (pintype "input"))
      (node (ref "IN5-6") (pin "14") (pinfunction "14_14") (pintype "passive"))
    )
    (net (code "118") (name "Net-(IC16A-4D)") (class "Default")
      (node (ref "IC16") (pin "8") (pinfunction "4D_8") (pintype "input"))
      (node (ref "IN5-6") (pin "16") (pinfunction "16_16") (pintype "passive"))
    )
    (net (code "119") (name "Net-(IC16A-5D)") (class "Default")
      (node (ref "IC16") (pin "13") (pinfunction "5D_13") (pintype "input"))
      (node (ref "IN5-6") (pin "9") (pinfunction "9_9") (pintype "passive"))
    )
    (net (code "120") (name "Net-(IC16A-6D)") (class "Default")
      (node (ref "IC16") (pin "14") (pinfunction "6D_14") (pintype "input"))
      (node (ref "IN5-6") (pin "11") (pinfunction "11_11") (pintype "passive"))
    )
    (net (code "121") (name "Net-(IC16A-7D)") (class "Default")
      (node (ref "IC16") (pin "17") (pinfunction "7D_17") (pintype "input"))
      (node (ref "IN5-6") (pin "13") (pinfunction "13_13") (pintype "passive"))
    )
    (net (code "122") (name "Net-(IC16A-8D)") (class "Default")
      (node (ref "IC16") (pin "18") (pinfunction "8D_18") (pintype "input"))
      (node (ref "IN5-6") (pin "15") (pinfunction "15_15") (pintype "passive"))
    )
    (net (code "123") (name "Net-(IC17A-1D)") (class "Default")
      (node (ref "IC17") (pin "3") (pinfunction "1D_3") (pintype "input"))
      (node (ref "IN7-8") (pin "2") (pinfunction "2_2") (pintype "passive"))
    )
    (net (code "124") (name "Net-(IC17A-2D)") (class "Default")
      (node (ref "IC17") (pin "4") (pinfunction "2D_4") (pintype "input"))
      (node (ref "IN7-8") (pin "4") (pinfunction "4_4") (pintype "passive"))
    )
    (net (code "125") (name "Net-(IC17A-3D)") (class "Default")
      (node (ref "IC17") (pin "7") (pinfunction "3D_7") (pintype "input"))
      (node (ref "IN7-8") (pin "6") (pinfunction "6_6") (pintype "passive"))
    )
    (net (code "126") (name "Net-(IC17A-4D)") (class "Default")
      (node (ref "IC17") (pin "8") (pinfunction "4D_8") (pintype "input"))
      (node (ref "IN7-8") (pin "8") (pinfunction "8_8") (pintype "passive"))
    )
    (net (code "127") (name "Net-(IC17A-5D)") (class "Default")
      (node (ref "IC17") (pin "13") (pinfunction "5D_13") (pintype "input"))
      (node (ref "IN7-8") (pin "1") (pinfunction "1_1") (pintype "passive"))
    )
    (net (code "128") (name "Net-(IC17A-6D)") (class "Default")
      (node (ref "IC17") (pin "14") (pinfunction "6D_14") (pintype "input"))
      (node (ref "IN7-8") (pin "3") (pinfunction "3_3") (pintype "passive"))
    )
    (net (code "129") (name "Net-(IC17A-7D)") (class "Default")
      (node (ref "IC17") (pin "17") (pinfunction "7D_17") (pintype "input"))
      (node (ref "IN7-8") (pin "5") (pinfunction "5_5") (pintype "passive"))
    )
    (net (code "130") (name "Net-(IC17A-8D)") (class "Default")
      (node (ref "IC17") (pin "18") (pinfunction "8D_18") (pintype "input"))
      (node (ref "IN7-8") (pin "7") (pinfunction "7_7") (pintype "passive"))
    )
    (net (code "131") (name "Net-(IC18A-1D)") (class "Default")
      (node (ref "IC18") (pin "3") (pinfunction "1D_3") (pintype "input"))
      (node (ref "IN7-8") (pin "10") (pinfunction "10_10") (pintype "passive"))
    )
    (net (code "132") (name "Net-(IC18A-2D)") (class "Default")
      (node (ref "IC18") (pin "4") (pinfunction "2D_4") (pintype "input"))
      (node (ref "IN7-8") (pin "12") (pinfunction "12_12") (pintype "passive"))
    )
    (net (code "133") (name "Net-(IC18A-3D)") (class "Default")
      (node (ref "IC18") (pin "7") (pinfunction "3D_7") (pintype "input"))
      (node (ref "IN7-8") (pin "14") (pinfunction "14_14") (pintype "passive"))
    )
    (net (code "134") (name "Net-(IC18A-4D)") (class "Default")
      (node (ref "IC18") (pin "8") (pinfunction "4D_8") (pintype "input"))
      (node (ref "IN7-8") (pin "16") (pinfunction "16_16") (pintype "passive"))
    )
    (net (code "135") (name "Net-(IC18A-5D)") (class "Default")
      (node (ref "IC18") (pin "13") (pinfunction "5D_13") (pintype "input"))
      (node (ref "IN7-8") (pin "9") (pinfunction "9_9") (pintype "passive"))
    )
    (net (code "136") (name "Net-(IC18A-6D)") (class "Default")
      (node (ref "IC18") (pin "14") (pinfunction "6D_14") (pintype "input"))
      (node (ref "IN7-8") (pin "11") (pinfunction "11_11") (pintype "passive"))
    )
    (net (code "137") (name "Net-(IC18A-7D)") (class "Default")
      (node (ref "IC18") (pin "17") (pinfunction "7D_17") (pintype "input"))
      (node (ref "IN7-8") (pin "13") (pinfunction "13_13") (pintype "passive"))
    )
    (net (code "138") (name "Net-(IC18A-8D)") (class "Default")
      (node (ref "IC18") (pin "18") (pinfunction "8D_18") (pintype "input"))
      (node (ref "IN7-8") (pin "15") (pinfunction "15_15") (pintype "passive"))
    )
    (net (code "139") (name "Net-(IC19A-Y0)") (class "Default")
      (node (ref "DEVSEL") (pin "18") (pinfunction "18_18") (pintype "passive"))
      (node (ref "IC19") (pin "15") (pinfunction "Y0_15") (pintype "output"))
    )
    (net (code "140") (name "Net-(IC19A-Y1)") (class "Default")
      (node (ref "DEVSEL") (pin "16") (pinfunction "16_16") (pintype "passive"))
      (node (ref "IC19") (pin "14") (pinfunction "Y1_14") (pintype "output"))
    )
    (net (code "141") (name "Net-(IC19A-Y2)") (class "Default")
      (node (ref "DEVSEL") (pin "14") (pinfunction "14_14") (pintype "passive"))
      (node (ref "IC19") (pin "13") (pinfunction "Y2_13") (pintype "output"))
    )
    (net (code "142") (name "Net-(IC19A-Y3)") (class "Default")
      (node (ref "DEVSEL") (pin "12") (pinfunction "12_12") (pintype "passive"))
      (node (ref "IC19") (pin "12") (pinfunction "Y3_12") (pintype "output"))
    )
    (net (code "143") (name "Net-(IC19A-Y4)") (class "Default")
      (node (ref "DEVSEL") (pin "10") (pinfunction "10_10") (pintype "passive"))
      (node (ref "IC19") (pin "11") (pinfunction "Y4_11") (pintype "output"))
    )
    (net (code "144") (name "Net-(IC19A-Y5)") (class "Default")
      (node (ref "DEVSEL") (pin "8") (pinfunction "8_8") (pintype "passive"))
      (node (ref "IC19") (pin "10") (pinfunction "Y5_10") (pintype "output"))
    )
    (net (code "145") (name "Net-(IC19A-Y6)") (class "Default")
      (node (ref "DEVSEL") (pin "6") (pinfunction "6_6") (pintype "passive"))
      (node (ref "IC19") (pin "9") (pinfunction "Y6_9") (pintype "output"))
    )
    (net (code "146") (name "Net-(IC19A-Y7)") (class "Default")
      (node (ref "DEVSEL") (pin "4") (pinfunction "4_4") (pintype "passive"))
      (node (ref "IC19") (pin "7") (pinfunction "Y7_7") (pintype "output"))
    )
    (net (code "147") (name "OUT00") (class "Default")
      (node (ref "IC1") (pin "11") (pinfunction "CLK_11") (pintype "input"))
      (node (ref "IC10") (pin "15") (pinfunction "Y0_15") (pintype "output"))
    )
    (net (code "148") (name "OUT01") (class "Default")
      (node (ref "IC10") (pin "14") (pinfunction "Y1_14") (pintype "output"))
      (node (ref "IC2") (pin "11") (pinfunction "CLK_11") (pintype "input"))
    )
    (net (code "149") (name "OUT02") (class "Default")
      (node (ref "IC10") (pin "13") (pinfunction "Y2_13") (pintype "output"))
      (node (ref "IC3") (pin "11") (pinfunction "CLK_11") (pintype "input"))
    )
    (net (code "150") (name "OUT03") (class "Default")
      (node (ref "IC10") (pin "12") (pinfunction "Y3_12") (pintype "output"))
      (node (ref "IC4") (pin "11") (pinfunction "CLK_11") (pintype "input"))
    )
    (net (code "151") (name "OUT04") (class "Default")
      (node (ref "IC10") (pin "11") (pinfunction "Y4_11") (pintype "output"))
      (node (ref "IC5") (pin "11") (pinfunction "CLK_11") (pintype "input"))
    )
    (net (code "152") (name "OUT05") (class "Default")
      (node (ref "IC10") (pin "10") (pinfunction "Y5_10") (pintype "output"))
      (node (ref "IC6") (pin "11") (pinfunction "CLK_11") (pintype "input"))
    )
    (net (code "153") (name "OUT06") (class "Default")
      (node (ref "IC10") (pin "9") (pinfunction "Y6_9") (pintype "output"))
      (node (ref "IC7") (pin "11") (pinfunction "CLK_11") (pintype "input"))
    )
    (net (code "154") (name "OUT07") (class "Default")
      (node (ref "IC10") (pin "7") (pinfunction "Y7_7") (pintype "output"))
      (node (ref "IC8") (pin "11") (pinfunction "CLK_11") (pintype "input"))
    )
    (net (code "155") (name "PIA-A0") (class "Default")
      (node (ref "CORE-IO") (pin "1") (pinfunction "1_1") (pintype "passive"))
      (node (ref "IC1") (pin "3") (pinfunction "1D_3") (pintype "input"))
      (node (ref "IC11") (pin "2") (pinfunction "1Q_2") (pintype "tri_state"))
      (node (ref "IC12") (pin "2") (pinfunction "1Q_2") (pintype "tri_state"))
      (node (ref "IC13") (pin "2") (pinfunction "1Q_2") (pintype "tri_state"))
      (node (ref "IC14") (pin "2") (pinfunction "1Q_2") (pintype "tri_state"))
      (node (ref "IC15") (pin "2") (pinfunction "1Q_2") (pintype "tri_state"))
      (node (ref "IC16") (pin "2") (pinfunction "1Q_2") (pintype "tri_state"))
      (node (ref "IC17") (pin "2") (pinfunction "1Q_2") (pintype "tri_state"))
      (node (ref "IC18") (pin "2") (pinfunction "1Q_2") (pintype "tri_state"))
      (node (ref "IC2") (pin "3") (pinfunction "1D_3") (pintype "input"))
      (node (ref "IC3") (pin "3") (pinfunction "1D_3") (pintype "input"))
      (node (ref "IC4") (pin "3") (pinfunction "1D_3") (pintype "input"))
      (node (ref "IC5") (pin "3") (pinfunction "1D_3") (pintype "input"))
      (node (ref "IC6") (pin "3") (pinfunction "1D_3") (pintype "input"))
      (node (ref "IC7") (pin "3") (pinfunction "1D_3") (pintype "input"))
      (node (ref "IC8") (pin "3") (pinfunction "1D_3") (pintype "input"))
    )
    (net (code "156") (name "PIA-A1") (class "Default")
      (node (ref "CORE-IO") (pin "2") (pinfunction "2_2") (pintype "passive"))
      (node (ref "IC1") (pin "4") (pinfunction "2D_4") (pintype "input"))
      (node (ref "IC11") (pin "5") (pinfunction "2Q_5") (pintype "tri_state"))
      (node (ref "IC12") (pin "5") (pinfunction "2Q_5") (pintype "tri_state"))
      (node (ref "IC13") (pin "5") (pinfunction "2Q_5") (pintype "tri_state"))
      (node (ref "IC14") (pin "5") (pinfunction "2Q_5") (pintype "tri_state"))
      (node (ref "IC15") (pin "5") (pinfunction "2Q_5") (pintype "tri_state"))
      (node (ref "IC16") (pin "5") (pinfunction "2Q_5") (pintype "tri_state"))
      (node (ref "IC17") (pin "5") (pinfunction "2Q_5") (pintype "tri_state"))
      (node (ref "IC18") (pin "5") (pinfunction "2Q_5") (pintype "tri_state"))
      (node (ref "IC2") (pin "4") (pinfunction "2D_4") (pintype "input"))
      (node (ref "IC3") (pin "4") (pinfunction "2D_4") (pintype "input"))
      (node (ref "IC4") (pin "4") (pinfunction "2D_4") (pintype "input"))
      (node (ref "IC5") (pin "4") (pinfunction "2D_4") (pintype "input"))
      (node (ref "IC6") (pin "4") (pinfunction "2D_4") (pintype "input"))
      (node (ref "IC7") (pin "4") (pinfunction "2D_4") (pintype "input"))
      (node (ref "IC8") (pin "4") (pinfunction "2D_4") (pintype "input"))
    )
    (net (code "157") (name "PIA-A2") (class "Default")
      (node (ref "CORE-IO") (pin "3") (pinfunction "3_3") (pintype "passive"))
      (node (ref "IC1") (pin "7") (pinfunction "3D_7") (pintype "input"))
      (node (ref "IC11") (pin "6") (pinfunction "3Q_6") (pintype "tri_state"))
      (node (ref "IC12") (pin "6") (pinfunction "3Q_6") (pintype "tri_state"))
      (node (ref "IC13") (pin "6") (pinfunction "3Q_6") (pintype "tri_state"))
      (node (ref "IC14") (pin "6") (pinfunction "3Q_6") (pintype "tri_state"))
      (node (ref "IC15") (pin "6") (pinfunction "3Q_6") (pintype "tri_state"))
      (node (ref "IC16") (pin "6") (pinfunction "3Q_6") (pintype "tri_state"))
      (node (ref "IC17") (pin "6") (pinfunction "3Q_6") (pintype "tri_state"))
      (node (ref "IC18") (pin "6") (pinfunction "3Q_6") (pintype "tri_state"))
      (node (ref "IC2") (pin "7") (pinfunction "3D_7") (pintype "input"))
      (node (ref "IC3") (pin "7") (pinfunction "3D_7") (pintype "input"))
      (node (ref "IC4") (pin "7") (pinfunction "3D_7") (pintype "input"))
      (node (ref "IC5") (pin "7") (pinfunction "3D_7") (pintype "input"))
      (node (ref "IC6") (pin "7") (pinfunction "3D_7") (pintype "input"))
      (node (ref "IC7") (pin "7") (pinfunction "3D_7") (pintype "input"))
      (node (ref "IC8") (pin "7") (pinfunction "3D_7") (pintype "input"))
    )
    (net (code "158") (name "PIA-A3") (class "Default")
      (node (ref "CORE-IO") (pin "4") (pinfunction "4_4") (pintype "passive"))
      (node (ref "IC1") (pin "8") (pinfunction "4D_8") (pintype "input"))
      (node (ref "IC11") (pin "9") (pinfunction "4Q_9") (pintype "tri_state"))
      (node (ref "IC12") (pin "9") (pinfunction "4Q_9") (pintype "tri_state"))
      (node (ref "IC13") (pin "9") (pinfunction "4Q_9") (pintype "tri_state"))
      (node (ref "IC14") (pin "9") (pinfunction "4Q_9") (pintype "tri_state"))
      (node (ref "IC15") (pin "9") (pinfunction "4Q_9") (pintype "tri_state"))
      (node (ref "IC16") (pin "9") (pinfunction "4Q_9") (pintype "tri_state"))
      (node (ref "IC17") (pin "9") (pinfunction "4Q_9") (pintype "tri_state"))
      (node (ref "IC18") (pin "9") (pinfunction "4Q_9") (pintype "tri_state"))
      (node (ref "IC2") (pin "8") (pinfunction "4D_8") (pintype "input"))
      (node (ref "IC3") (pin "8") (pinfunction "4D_8") (pintype "input"))
      (node (ref "IC4") (pin "8") (pinfunction "4D_8") (pintype "input"))
      (node (ref "IC5") (pin "8") (pinfunction "4D_8") (pintype "input"))
      (node (ref "IC6") (pin "8") (pinfunction "4D_8") (pintype "input"))
      (node (ref "IC7") (pin "8") (pinfunction "4D_8") (pintype "input"))
      (node (ref "IC8") (pin "8") (pinfunction "4D_8") (pintype "input"))
    )
    (net (code "159") (name "PIA-A4") (class "Default")
      (node (ref "CORE-IO") (pin "5") (pinfunction "5_5") (pintype "passive"))
      (node (ref "IC1") (pin "13") (pinfunction "5D_13") (pintype "input"))
      (node (ref "IC11") (pin "12") (pinfunction "5Q_12") (pintype "tri_state"))
      (node (ref "IC12") (pin "12") (pinfunction "5Q_12") (pintype "tri_state"))
      (node (ref "IC13") (pin "12") (pinfunction "5Q_12") (pintype "tri_state"))
      (node (ref "IC14") (pin "12") (pinfunction "5Q_12") (pintype "tri_state"))
      (node (ref "IC15") (pin "12") (pinfunction "5Q_12") (pintype "tri_state"))
      (node (ref "IC16") (pin "12") (pinfunction "5Q_12") (pintype "tri_state"))
      (node (ref "IC17") (pin "12") (pinfunction "5Q_12") (pintype "tri_state"))
      (node (ref "IC18") (pin "12") (pinfunction "5Q_12") (pintype "tri_state"))
      (node (ref "IC2") (pin "13") (pinfunction "5D_13") (pintype "input"))
      (node (ref "IC3") (pin "13") (pinfunction "5D_13") (pintype "input"))
      (node (ref "IC4") (pin "13") (pinfunction "5D_13") (pintype "input"))
      (node (ref "IC5") (pin "13") (pinfunction "5D_13") (pintype "input"))
      (node (ref "IC6") (pin "13") (pinfunction "5D_13") (pintype "input"))
      (node (ref "IC7") (pin "13") (pinfunction "5D_13") (pintype "input"))
      (node (ref "IC8") (pin "13") (pinfunction "5D_13") (pintype "input"))
    )
    (net (code "160") (name "PIA-A5") (class "Default")
      (node (ref "CORE-IO") (pin "6") (pinfunction "6_6") (pintype "passive"))
      (node (ref "IC1") (pin "14") (pinfunction "6D_14") (pintype "input"))
      (node (ref "IC11") (pin "15") (pinfunction "6Q_15") (pintype "tri_state"))
      (node (ref "IC12") (pin "15") (pinfunction "6Q_15") (pintype "tri_state"))
      (node (ref "IC13") (pin "15") (pinfunction "6Q_15") (pintype "tri_state"))
      (node (ref "IC14") (pin "15") (pinfunction "6Q_15") (pintype "tri_state"))
      (node (ref "IC15") (pin "15") (pinfunction "6Q_15") (pintype "tri_state"))
      (node (ref "IC16") (pin "15") (pinfunction "6Q_15") (pintype "tri_state"))
      (node (ref "IC17") (pin "15") (pinfunction "6Q_15") (pintype "tri_state"))
      (node (ref "IC18") (pin "15") (pinfunction "6Q_15") (pintype "tri_state"))
      (node (ref "IC2") (pin "14") (pinfunction "6D_14") (pintype "input"))
      (node (ref "IC3") (pin "14") (pinfunction "6D_14") (pintype "input"))
      (node (ref "IC4") (pin "14") (pinfunction "6D_14") (pintype "input"))
      (node (ref "IC5") (pin "14") (pinfunction "6D_14") (pintype "input"))
      (node (ref "IC6") (pin "14") (pinfunction "6D_14") (pintype "input"))
      (node (ref "IC7") (pin "14") (pinfunction "6D_14") (pintype "input"))
      (node (ref "IC8") (pin "14") (pinfunction "6D_14") (pintype "input"))
    )
    (net (code "161") (name "PIA-A6") (class "Default")
      (node (ref "CORE-IO") (pin "7") (pinfunction "7_7") (pintype "passive"))
      (node (ref "IC1") (pin "17") (pinfunction "7D_17") (pintype "input"))
      (node (ref "IC11") (pin "16") (pinfunction "7Q_16") (pintype "tri_state"))
      (node (ref "IC12") (pin "16") (pinfunction "7Q_16") (pintype "tri_state"))
      (node (ref "IC13") (pin "16") (pinfunction "7Q_16") (pintype "tri_state"))
      (node (ref "IC14") (pin "16") (pinfunction "7Q_16") (pintype "tri_state"))
      (node (ref "IC15") (pin "16") (pinfunction "7Q_16") (pintype "tri_state"))
      (node (ref "IC16") (pin "16") (pinfunction "7Q_16") (pintype "tri_state"))
      (node (ref "IC17") (pin "16") (pinfunction "7Q_16") (pintype "tri_state"))
      (node (ref "IC18") (pin "16") (pinfunction "7Q_16") (pintype "tri_state"))
      (node (ref "IC2") (pin "17") (pinfunction "7D_17") (pintype "input"))
      (node (ref "IC3") (pin "17") (pinfunction "7D_17") (pintype "input"))
      (node (ref "IC4") (pin "17") (pinfunction "7D_17") (pintype "input"))
      (node (ref "IC5") (pin "17") (pinfunction "7D_17") (pintype "input"))
      (node (ref "IC6") (pin "17") (pinfunction "7D_17") (pintype "input"))
      (node (ref "IC7") (pin "17") (pinfunction "7D_17") (pintype "input"))
      (node (ref "IC8") (pin "17") (pinfunction "7D_17") (pintype "input"))
    )
    (net (code "162") (name "PIA-A7") (class "Default")
      (node (ref "CORE-IO") (pin "8") (pinfunction "8_8") (pintype "passive"))
      (node (ref "IC1") (pin "18") (pinfunction "8D_18") (pintype "input"))
      (node (ref "IC11") (pin "19") (pinfunction "8Q_19") (pintype "tri_state"))
      (node (ref "IC12") (pin "19") (pinfunction "8Q_19") (pintype "tri_state"))
      (node (ref "IC13") (pin "19") (pinfunction "8Q_19") (pintype "tri_state"))
      (node (ref "IC14") (pin "19") (pinfunction "8Q_19") (pintype "tri_state"))
      (node (ref "IC15") (pin "19") (pinfunction "8Q_19") (pintype "tri_state"))
      (node (ref "IC16") (pin "19") (pinfunction "8Q_19") (pintype "tri_state"))
      (node (ref "IC17") (pin "19") (pinfunction "8Q_19") (pintype "tri_state"))
      (node (ref "IC18") (pin "19") (pinfunction "8Q_19") (pintype "tri_state"))
      (node (ref "IC2") (pin "18") (pinfunction "8D_18") (pintype "input"))
      (node (ref "IC3") (pin "18") (pinfunction "8D_18") (pintype "input"))
      (node (ref "IC4") (pin "18") (pinfunction "8D_18") (pintype "input"))
      (node (ref "IC5") (pin "18") (pinfunction "8D_18") (pintype "input"))
      (node (ref "IC6") (pin "18") (pinfunction "8D_18") (pintype "input"))
      (node (ref "IC7") (pin "18") (pinfunction "8D_18") (pintype "input"))
      (node (ref "IC8") (pin "18") (pinfunction "8D_18") (pintype "input"))
    )
    (net (code "163") (name "PIA-B0") (class "Default")
      (node (ref "CORE-IO") (pin "13") (pinfunction "13_13") (pintype "passive"))
      (node (ref "IC10") (pin "1") (pinfunction "A_1") (pintype "input"))
      (node (ref "IC9") (pin "1") (pinfunction "A_1") (pintype "input"))
    )
    (net (code "164") (name "PIA-B1") (class "Default")
      (node (ref "CORE-IO") (pin "14") (pinfunction "14_14") (pintype "passive"))
      (node (ref "IC10") (pin "2") (pinfunction "B_2") (pintype "input"))
      (node (ref "IC9") (pin "2") (pinfunction "B_2") (pintype "input"))
    )
    (net (code "165") (name "PIA-B2") (class "Default")
      (node (ref "CORE-IO") (pin "15") (pinfunction "15_15") (pintype "passive"))
      (node (ref "IC10") (pin "3") (pinfunction "C_3") (pintype "input"))
      (node (ref "IC9") (pin "3") (pinfunction "C_3") (pintype "input"))
    )
    (net (code "166") (name "PIA-B3") (class "Default")
      (node (ref "CORE-IO") (pin "16") (pinfunction "16_16") (pintype "passive"))
      (node (ref "IC19") (pin "1") (pinfunction "A_1") (pintype "input"))
    )
    (net (code "167") (name "PIA-B4") (class "Default")
      (node (ref "CORE-IO") (pin "17") (pinfunction "17_17") (pintype "passive"))
      (node (ref "IC19") (pin "2") (pinfunction "B_2") (pintype "input"))
    )
    (net (code "168") (name "PIA-B5") (class "Default")
      (node (ref "CORE-IO") (pin "18") (pinfunction "18_18") (pintype "passive"))
      (node (ref "IC19") (pin "3") (pinfunction "C_3") (pintype "input"))
    )
    (net (code "169") (name "PIA-B6") (class "Default")
      (node (ref "CORE-IO") (pin "19") (pinfunction "19_19") (pintype "passive"))
      (node (ref "IC10") (pin "6") (pinfunction "G1_6") (pintype "input"))
      (node (ref "IC9") (pin "4") (pinfunction "G2A_4") (pintype "input"))
    )
    (net (code "170") (name "PIA-B7") (class "Default")
      (node (ref "CORE-IO") (pin "20") (pinfunction "20_20") (pintype "passive"))
      (node (ref "DEVSEL") (pin "2") (pinfunction "2_2") (pintype "passive"))
      (node (ref "IC19") (pin "5") (pinfunction "G2B_5") (pintype "input"))
    )
    (net (code "171") (name "VCC") (class "Default")
      (node (ref "BYP1") (pin "1") (pinfunction "1_1") (pintype "passive"))
      (node (ref "BYP10") (pin "1") (pinfunction "1_1") (pintype "passive"))
      (node (ref "BYP11") (pin "1") (pinfunction "1_1") (pintype "passive"))
      (node (ref "BYP12") (pin "1") (pinfunction "1_1") (pintype "passive"))
      (node (ref "BYP13") (pin "1") (pinfunction "1_1") (pintype "passive"))
      (node (ref "BYP14") (pin "1") (pinfunction "1_1") (pintype "passive"))
      (node (ref "BYP15") (pin "1") (pinfunction "1_1") (pintype "passive"))
      (node (ref "BYP16") (pin "1") (pinfunction "1_1") (pintype "passive"))
      (node (ref "BYP17") (pin "1") (pinfunction "1_1") (pintype "passive"))
      (node (ref "BYP18") (pin "1") (pinfunction "1_1") (pintype "passive"))
      (node (ref "BYP19") (pin "1") (pinfunction "1_1") (pintype "passive"))
      (node (ref "BYP2") (pin "1") (pinfunction "1_1") (pintype "passive"))
      (node (ref "BYP20") (pin "1") (pinfunction "1_1") (pintype "passive"))
      (node (ref "BYP3") (pin "1") (pinfunction "1_1") (pintype "passive"))
      (node (ref "BYP4") (pin "1") (pinfunction "1_1") (pintype "passive"))
      (node (ref "BYP5") (pin "1") (pinfunction "1_1") (pintype "passive"))
      (node (ref "BYP6") (pin "1") (pinfunction "1_1") (pintype "passive"))
      (node (ref "BYP7") (pin "1") (pinfunction "1_1") (pintype "passive"))
      (node (ref "BYP8") (pin "1") (pinfunction "1_1") (pintype "passive"))
      (node (ref "BYP9") (pin "1") (pinfunction "1_1") (pintype "passive"))
      (node (ref "CORE-IO") (pin "12") (pinfunction "12_12") (pintype "passive"))
      (node (ref "CORE-IO") (pin "9") (pinfunction "9_9") (pintype "passive"))
      (node (ref "IC11") (pin "11") (pinfunction "ENC_11") (pintype "input"))
      (node (ref "IC12") (pin "11") (pinfunction "ENC_11") (pintype "input"))
      (node (ref "IC13") (pin "11") (pinfunction "ENC_11") (pintype "input"))
      (node (ref "IC14") (pin "11") (pinfunction "ENC_11") (pintype "input"))
      (node (ref "IC15") (pin "11") (pinfunction "ENC_11") (pintype "input"))
      (node (ref "IC16") (pin "11") (pinfunction "ENC_11") (pintype "input"))
      (node (ref "IC17") (pin "11") (pinfunction "ENC_11") (pintype "input"))
      (node (ref "IC18") (pin "11") (pinfunction "ENC_11") (pintype "input"))
      (node (ref "IC19") (pin "6") (pinfunction "G1_6") (pintype "input"))
      (node (ref "IC9") (pin "6") (pinfunction "G1_6") (pintype "input"))
      (node (ref "JP2") (pin "2") (pinfunction "2_2") (pintype "passive"))
    )
    (net (code "172") (name "unconnected-(IC20A-CLK-Pad11)") (class "Default")
      (node (ref "IC20") (pin "11") (pinfunction "CLK_11") (pintype "input"))
    )
    (net (code "173") (name "unconnected-(IC20A-CLR-Pad1)") (class "Default")
      (node (ref "IC20") (pin "1") (pinfunction "CLR_1") (pintype "input"))
    )
    (net (code "174") (name "unconnected-(IC20A-D1-Pad3)") (class "Default")
      (node (ref "IC20") (pin "3") (pinfunction "D1_3") (pintype "input"))
    )
    (net (code "175") (name "unconnected-(IC20A-D2-Pad4)") (class "Default")
      (node (ref "IC20") (pin "4") (pinfunction "D2_4") (pintype "input"))
    )
    (net (code "176") (name "unconnected-(IC20A-D3-Pad7)") (class "Default")
      (node (ref "IC20") (pin "7") (pinfunction "D3_7") (pintype "input"))
    )
    (net (code "177") (name "unconnected-(IC20A-D4-Pad8)") (class "Default")
      (node (ref "IC20") (pin "8") (pinfunction "D4_8") (pintype "input"))
    )
    (net (code "178") (name "unconnected-(IC20A-D5-Pad13)") (class "Default")
      (node (ref "IC20") (pin "13") (pinfunction "D5_13") (pintype "input"))
    )
    (net (code "179") (name "unconnected-(IC20A-D6-Pad14)") (class "Default")
      (node (ref "IC20") (pin "14") (pinfunction "D6_14") (pintype "input"))
    )
    (net (code "180") (name "unconnected-(IC20A-D7-Pad17)") (class "Default")
      (node (ref "IC20") (pin "17") (pinfunction "D7_17") (pintype "input"))
    )
    (net (code "181") (name "unconnected-(IC20A-D8-Pad18)") (class "Default")
      (node (ref "IC20") (pin "18") (pinfunction "D8_18") (pintype "input"))
    )
    (net (code "182") (name "unconnected-(IC20A-Q1-Pad2)") (class "Default")
      (node (ref "IC20") (pin "2") (pinfunction "Q1_2") (pintype "output"))
    )
    (net (code "183") (name "unconnected-(IC20A-Q2-Pad5)") (class "Default")
      (node (ref "IC20") (pin "5") (pinfunction "Q2_5") (pintype "output"))
    )
    (net (code "184") (name "unconnected-(IC20A-Q3-Pad6)") (class "Default")
      (node (ref "IC20") (pin "6") (pinfunction "Q3_6") (pintype "output"))
    )
    (net (code "185") (name "unconnected-(IC20A-Q4-Pad9)") (class "Default")
      (node (ref "IC20") (pin "9") (pinfunction "Q4_9") (pintype "output"))
    )
    (net (code "186") (name "unconnected-(IC20A-Q5-Pad12)") (class "Default")
      (node (ref "IC20") (pin "12") (pinfunction "Q5_12") (pintype "output"))
    )
    (net (code "187") (name "unconnected-(IC20A-Q6-Pad15)") (class "Default")
      (node (ref "IC20") (pin "15") (pinfunction "Q6_15") (pintype "output"))
    )
    (net (code "188") (name "unconnected-(IC20A-Q7-Pad16)") (class "Default")
      (node (ref "IC20") (pin "16") (pinfunction "Q7_16") (pintype "output"))
    )
    (net (code "189") (name "unconnected-(IC20A-Q8-Pad19)") (class "Default")
      (node (ref "IC20") (pin "19") (pinfunction "Q8_19") (pintype "output"))
    )
  )
)
